# esp_coaster.net
KiCad netlist of a schematic drawn in EAGLE
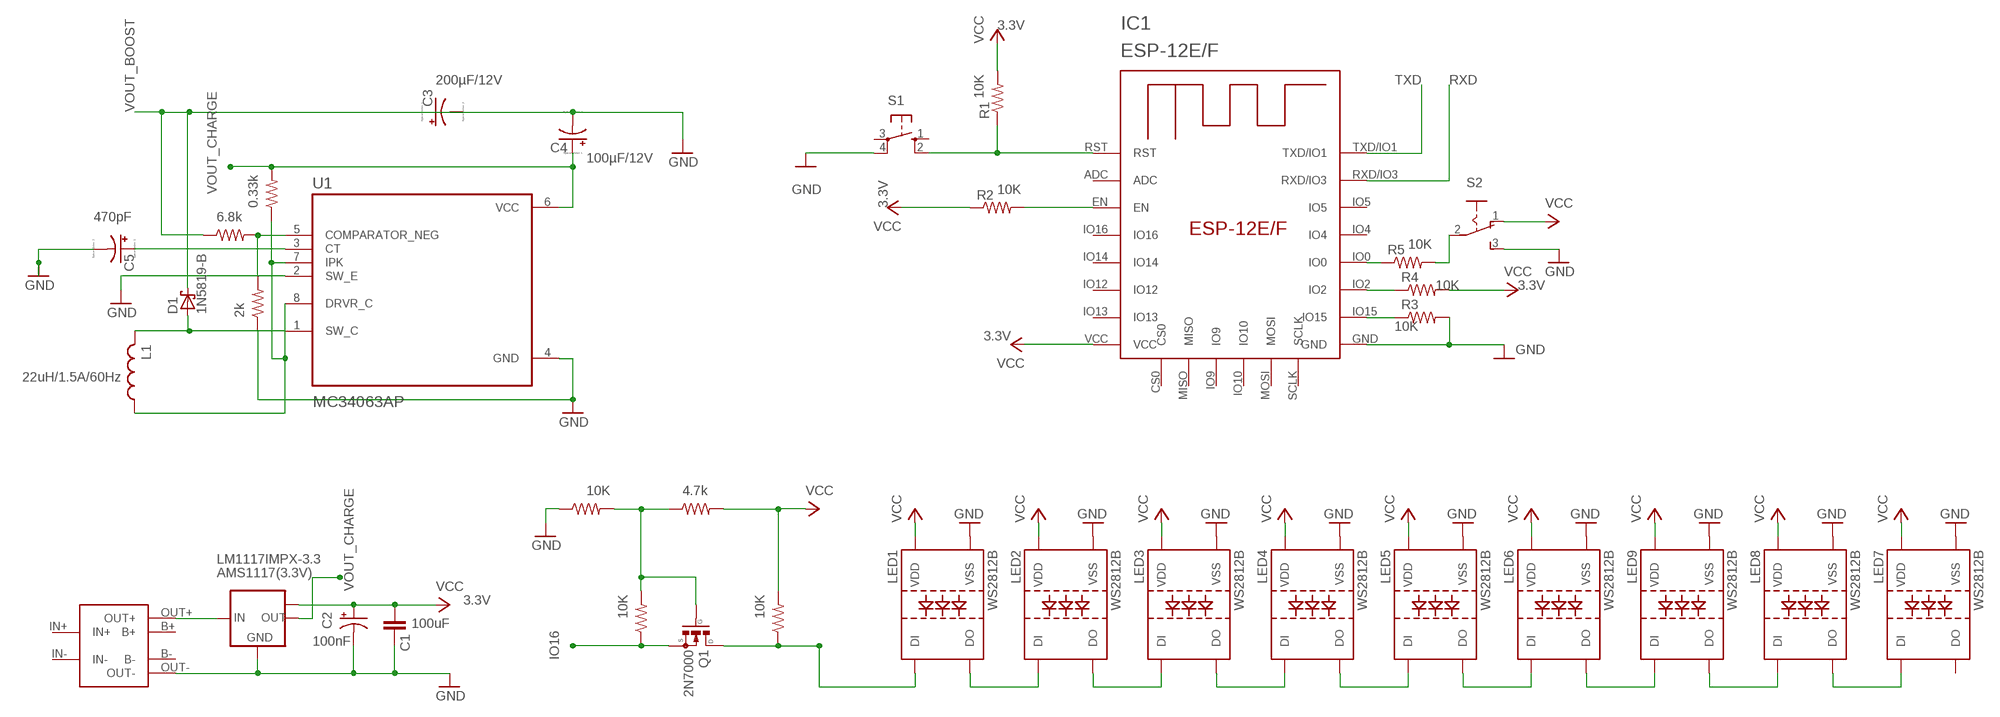
[diagram p0: schematic, sheet 1]

(export (version "E")
  (design (tool "Eeschema 10.0.6"))
  (components
    (comp (ref "AMS1117(3.3V)")
      (value "LM1117IMPX-3.3")
      (footprint "eagle-import:SOT223")
      (libsource (lib "eagle-import") (part "LM1117IMPX-3.3"))
    )
    (comp (ref "C1")
      (value "C-EUC1808")
      (footprint "eagle-import:C1808")
      (fields (field (name "POPULARITY") "0") (field (name "POPULARITY_1") "100uF"))
      (libsource (lib "eagle-import") (part "C-EUC1808"))
    )
    (comp (ref "C2")
      (value "CPOL-US139CLL-2R")
      (footprint "eagle-import:139CLL-2R")
      (fields (field (name "POPULARITY") "0") (field (name "POPULARITY_1") "100nF"))
      (libsource (lib "eagle-import") (part "CPOL-US139CLL-2R"))
    )
    (comp (ref "C3")
      (value "CPOL-US085CS-1AR")
      (footprint "eagle-import:085CS_1AR")
      (fields (field (name "C1") "200µF/12V"))
      (libsource (lib "eagle-import") (part "resistor_348_CPOL-US085CS-1AR"))
    )
    (comp (ref "C4")
      (value "CPOL-US085CS-1AR")
      (footprint "eagle-import:085CS_1AR")
      (fields (field (name "C2") "100µF/12V"))
      (libsource (lib "eagle-import") (part "resistor_348_CPOL-US085CS-1AR"))
    )
    (comp (ref "C5")
      (value "CPOL-US085CS-1AR")
      (footprint "eagle-import:085CS_1AR")
      (fields (field (name "CAPACITOR") "470pF"))
      (libsource (lib "eagle-import") (part "resistor_348_CPOL-US085CS-1AR"))
    )
    (comp (ref "D1")
      (value "1N5819-B")
      (footprint "eagle-import:DO41-7.6")
      (libsource (lib "eagle-import") (part "1N5819-B"))
    )
    (comp (ref "IC1")
      (value "ESP-12E/F")
      (footprint "eagle-import:ESP-12E")
      (libsource (lib "eagle-import") (part "ESP-12E/F"))
    )
    (comp (ref "L1")
      (value "L-US0204/5")
      (footprint "eagle-import:0204_5")
      (fields (field (name "INDUCTOR") "22uH/1.5A/60Hz"))
      (libsource (lib "eagle-import") (part "L-US0204/5"))
    )
    (comp (ref "LED1")
      (value "WS2812B")
      (footprint "eagle-import:WS2812B")
      (libsource (lib "eagle-import") (part "WS2812B"))
    )
    (comp (ref "LED2")
      (value "WS2812B")
      (footprint "eagle-import:WS2812B")
      (libsource (lib "eagle-import") (part "WS2812B"))
    )
    (comp (ref "LED3")
      (value "WS2812B")
      (footprint "eagle-import:WS2812B")
      (libsource (lib "eagle-import") (part "WS2812B"))
    )
    (comp (ref "LED4")
      (value "WS2812B")
      (footprint "eagle-import:WS2812B")
      (libsource (lib "eagle-import") (part "WS2812B"))
    )
    (comp (ref "LED5")
      (value "WS2812B")
      (footprint "eagle-import:WS2812B")
      (libsource (lib "eagle-import") (part "WS2812B"))
    )
    (comp (ref "LED6")
      (value "WS2812B")
      (footprint "eagle-import:WS2812B")
      (libsource (lib "eagle-import") (part "WS2812B"))
    )
    (comp (ref "LED7")
      (value "WS2812B")
      (footprint "eagle-import:WS2812B")
      (libsource (lib "eagle-import") (part "WS2812B"))
    )
    (comp (ref "LED8")
      (value "WS2812B")
      (footprint "eagle-import:WS2812B")
      (libsource (lib "eagle-import") (part "WS2812B"))
    )
    (comp (ref "LED9")
      (value "WS2812B")
      (footprint "eagle-import:WS2812B")
      (libsource (lib "eagle-import") (part "WS2812B"))
    )
    (comp (ref "Q1")
      (value "2N7000")
      (footprint "eagle-import:TO92")
      (fields (field (name "MF") "STMicroelectronics"))
      (libsource (lib "eagle-import") (part "2N7000"))
    )
    (comp (ref "R1")
      (value "R-US_M2309")
      (footprint "eagle-import:M2309")
      (fields (field (name "POPULARITY") "0") (field (name "POPULARITY_1") "10K"))
      (libsource (lib "eagle-import") (part "R-US_M2309"))
    )
    (comp (ref "R2")
      (value "R-US_M2309")
      (footprint "eagle-import:M2309")
      (fields (field (name "POPULARITY") "0") (field (name "POPULARITY_1") "10K"))
      (libsource (lib "eagle-import") (part "R-US_M2309"))
    )
    (comp (ref "R3")
      (value "R-US_M2309")
      (footprint "eagle-import:M2309")
      (fields (field (name "POPULARITY") "0") (field (name "POPULARITY_1") "10K"))
      (libsource (lib "eagle-import") (part "R-US_M2309"))
    )
    (comp (ref "R4")
      (value "R-US_M2309")
      (footprint "eagle-import:M2309")
      (fields (field (name "POPULARITY") "0") (field (name "POPULARITY_1") "10K"))
      (libsource (lib "eagle-import") (part "R-US_M2309"))
    )
    (comp (ref "R5")
      (value "R-US_M2309")
      (footprint "eagle-import:M2309")
      (fields (field (name "POPULARITY") "0") (field (name "POPULARITY_1") "10K"))
      (libsource (lib "eagle-import") (part "R-US_M2309"))
    )
    (comp (ref "R6")
      (value "R-US_M2309")
      (footprint "eagle-import:M2309")
      (fields (field (name "POPULARITY") "0") (field (name "POPULARITY_1") "6.8k"))
      (libsource (lib "eagle-import") (part "R-US_M2309"))
    )
    (comp (ref "R7")
      (value "R-US_M2309")
      (footprint "eagle-import:M2309")
      (fields (field (name "POPULARITY") "0") (field (name "POPULARITY_1") "2k"))
      (libsource (lib "eagle-import") (part "R-US_M2309"))
    )
    (comp (ref "R8")
      (value "R-US_M2309")
      (footprint "eagle-import:M2309")
      (fields (field (name "POPULARITY") "0") (field (name "POPULARITY_1") "0.33k"))
      (libsource (lib "eagle-import") (part "R-US_M2309"))
    )
    (comp (ref "R9")
      (value "R-US_M2309")
      (footprint "eagle-import:M2309")
      (fields (field (name "POPULARITY") "0") (field (name "POPULARITY_1") "10K"))
      (libsource (lib "eagle-import") (part "R-US_M2309"))
    )
    (comp (ref "R10")
      (value "R-US_M2309")
      (footprint "eagle-import:M2309")
      (fields (field (name "POPULARITY") "0") (field (name "POPULARITY_1") "4.7k"))
      (libsource (lib "eagle-import") (part "R-US_M2309"))
    )
    (comp (ref "R11")
      (value "R-US_M2309")
      (footprint "eagle-import:M2309")
      (fields (field (name "POPULARITY") "0") (field (name "POPULARITY_1") "10K"))
      (libsource (lib "eagle-import") (part "R-US_M2309"))
    )
    (comp (ref "R12")
      (value "R-US_M2309")
      (footprint "eagle-import:M2309")
      (fields (field (name "POPULARITY") "0") (field (name "POPULARITY_1") "10K"))
      (libsource (lib "eagle-import") (part "R-US_M2309"))
    )
    (comp (ref "S1")
      (value "10-XX")
      (footprint "eagle-import:B3F-10XX")
      (fields (field (name "MPN") "B3F-1000"))
      (libsource (lib "eagle-import") (part "10-XX"))
    )
    (comp (ref "S2")
      (value "255SB")
      (footprint "eagle-import:255SB")
      (libsource (lib "eagle-import") (part "255SB"))
    )
    (comp (ref "U$1")
      (value "TP4056")
      (footprint "eagle-import:TP4056")
      (libsource (lib "eagle-import") (part "TP4056"))
    )
    (comp (ref "U1")
      (value "MC34063AP")
      (footprint "eagle-import:DIP794W45P254L959H508Q8")
      (fields (field (name "MF") "Texas Instruments"))
      (libsource (lib "eagle-import") (part "MC34063AP"))
    )
  )
  (nets
    (net (code "1") (name "/IO16") (class "Default")
      (node (ref "Q1") (pin "1") (pinfunction "S_1") (pintype "passive"))
      (node (ref "R12") (pin "1") (pinfunction "1_1") (pintype "passive"))
    )
    (net (code "2") (name "/RXD") (class "Default")
      (node (ref "IC1") (pin "RXD/IO3") (pinfunction "RXD/IO3_RXD/IO3") (pintype "bidirectional"))
    )
    (net (code "3") (name "/TXD") (class "Default")
      (node (ref "IC1") (pin "TXD/IO1") (pinfunction "TXD/IO1_TXD/IO1") (pintype "bidirectional"))
    )
    (net (code "4") (name "/VOUT_BOOST") (class "Default")
      (node (ref "C3") (pin "-") (pinfunction "-_-") (pintype "passive"))
      (node (ref "D1") (pin "C") (pinfunction "C_C") (pintype "passive"))
      (node (ref "R6") (pin "1") (pinfunction "1_1") (pintype "passive"))
    )
    (net (code "5") (name "/VOUT_CHARGE") (class "Default")
      (node (ref "AMS1117(3.3V)") (pin "2") (pinfunction "OUT_2") (pintype "passive"))
      (node (ref "C4") (pin "+") (pinfunction "+_+") (pintype "passive"))
      (node (ref "R8") (pin "2") (pinfunction "2_2") (pintype "passive"))
      (node (ref "U1") (pin "6") (pinfunction "VCC_6") (pintype "power_in"))
    )
    (net (code "6") (name "GND") (class "Default")
      (node (ref "AMS1117(3.3V)") (pin "1") (pinfunction "GND_1") (pintype "input"))
      (node (ref "C1") (pin "1") (pinfunction "1_1") (pintype "passive"))
      (node (ref "C2") (pin "-") (pinfunction "-_-") (pintype "passive"))
      (node (ref "C3") (pin "+") (pinfunction "+_+") (pintype "passive"))
      (node (ref "C4") (pin "-") (pinfunction "-_-") (pintype "passive"))
      (node (ref "C5") (pin "-") (pinfunction "-_-") (pintype "passive"))
      (node (ref "IC1") (pin "GND") (pinfunction "GND_GND") (pintype "power_in"))
      (node (ref "LED1") (pin "3") (pinfunction "VSS_3") (pintype "bidirectional"))
      (node (ref "LED2") (pin "3") (pinfunction "VSS_3") (pintype "bidirectional"))
      (node (ref "LED3") (pin "3") (pinfunction "VSS_3") (pintype "bidirectional"))
      (node (ref "LED4") (pin "3") (pinfunction "VSS_3") (pintype "bidirectional"))
      (node (ref "LED5") (pin "3") (pinfunction "VSS_3") (pintype "bidirectional"))
      (node (ref "LED6") (pin "3") (pinfunction "VSS_3") (pintype "bidirectional"))
      (node (ref "LED7") (pin "3") (pinfunction "VSS_3") (pintype "bidirectional"))
      (node (ref "LED8") (pin "3") (pinfunction "VSS_3") (pintype "bidirectional"))
      (node (ref "LED9") (pin "3") (pinfunction "VSS_3") (pintype "bidirectional"))
      (node (ref "R11") (pin "1") (pinfunction "1_1") (pintype "passive"))
      (node (ref "R3") (pin "2") (pinfunction "2_2") (pintype "passive"))
      (node (ref "R7") (pin "1") (pinfunction "1_1") (pintype "passive"))
      (node (ref "S1") (pin "4") (pinfunction "P1_4") (pintype "passive"))
      (node (ref "S2") (pin "3") (pinfunction "S_3") (pintype "passive"))
      (node (ref "U$1") (pin "OUT-") (pinfunction "OUT-_OUT-") (pintype "bidirectional"))
      (node (ref "U1") (pin "2") (pinfunction "SW_E_2") (pintype "input"))
      (node (ref "U1") (pin "4") (pinfunction "GND_4") (pintype "power_in"))
    )
    (net (code "7") (name "Net-(AMS1117(3.3V)-IN)") (class "Default")
      (node (ref "AMS1117(3.3V)") (pin "3") (pinfunction "IN_3") (pintype "input"))
      (node (ref "U$1") (pin "OUT+") (pinfunction "OUT+_OUT+") (pintype "bidirectional"))
    )
    (net (code "8") (name "Net-(IC1-PadEN)") (class "Default")
      (node (ref "IC1") (pin "EN") (pinfunction "EN_EN") (pintype "bidirectional"))
      (node (ref "R2") (pin "2") (pinfunction "2_2") (pintype "passive"))
    )
    (net (code "9") (name "Net-(IC1-PadIO0)") (class "Default")
      (node (ref "IC1") (pin "IO0") (pinfunction "IO0_IO0") (pintype "bidirectional"))
      (node (ref "R5") (pin "1") (pinfunction "1_1") (pintype "passive"))
    )
    (net (code "10") (name "Net-(IC1-PadIO2)") (class "Default")
      (node (ref "IC1") (pin "IO2") (pinfunction "IO2_IO2") (pintype "bidirectional"))
      (node (ref "R4") (pin "1") (pinfunction "1_1") (pintype "passive"))
    )
    (net (code "11") (name "Net-(IC1-PadIO15)") (class "Default")
      (node (ref "IC1") (pin "IO15") (pinfunction "IO15_IO15") (pintype "bidirectional"))
      (node (ref "R3") (pin "1") (pinfunction "1_1") (pintype "passive"))
    )
    (net (code "12") (name "Net-(LED1-DI)") (class "Default")
      (node (ref "LED1") (pin "4") (pinfunction "DI_4") (pintype "bidirectional"))
      (node (ref "Q1") (pin "3") (pinfunction "D_3") (pintype "passive"))
      (node (ref "R9") (pin "1") (pinfunction "1_1") (pintype "passive"))
    )
    (net (code "13") (name "Net-(LED1-DO)") (class "Default")
      (node (ref "LED1") (pin "2") (pinfunction "DO_2") (pintype "bidirectional"))
      (node (ref "LED2") (pin "4") (pinfunction "DI_4") (pintype "bidirectional"))
    )
    (net (code "14") (name "Net-(LED2-DO)") (class "Default")
      (node (ref "LED2") (pin "2") (pinfunction "DO_2") (pintype "bidirectional"))
      (node (ref "LED3") (pin "4") (pinfunction "DI_4") (pintype "bidirectional"))
    )
    (net (code "15") (name "Net-(LED3-DO)") (class "Default")
      (node (ref "LED3") (pin "2") (pinfunction "DO_2") (pintype "bidirectional"))
      (node (ref "LED4") (pin "4") (pinfunction "DI_4") (pintype "bidirectional"))
    )
    (net (code "16") (name "Net-(LED4-DO)") (class "Default")
      (node (ref "LED4") (pin "2") (pinfunction "DO_2") (pintype "bidirectional"))
      (node (ref "LED5") (pin "4") (pinfunction "DI_4") (pintype "bidirectional"))
    )
    (net (code "17") (name "Net-(LED5-DO)") (class "Default")
      (node (ref "LED5") (pin "2") (pinfunction "DO_2") (pintype "bidirectional"))
      (node (ref "LED6") (pin "4") (pinfunction "DI_4") (pintype "bidirectional"))
    )
    (net (code "18") (name "Net-(LED6-DO)") (class "Default")
      (node (ref "LED6") (pin "2") (pinfunction "DO_2") (pintype "bidirectional"))
      (node (ref "LED9") (pin "4") (pinfunction "DI_4") (pintype "bidirectional"))
    )
    (net (code "19") (name "Net-(LED7-DI)") (class "Default")
      (node (ref "LED7") (pin "4") (pinfunction "DI_4") (pintype "bidirectional"))
      (node (ref "LED8") (pin "2") (pinfunction "DO_2") (pintype "bidirectional"))
    )
    (net (code "20") (name "Net-(LED8-DI)") (class "Default")
      (node (ref "LED8") (pin "4") (pinfunction "DI_4") (pintype "bidirectional"))
      (node (ref "LED9") (pin "2") (pinfunction "DO_2") (pintype "bidirectional"))
    )
    (net (code "21") (name "Net-(Q1-G)") (class "Default")
      (node (ref "Q1") (pin "2") (pinfunction "G_2") (pintype "passive"))
      (node (ref "R10") (pin "1") (pinfunction "1_1") (pintype "passive"))
      (node (ref "R11") (pin "2") (pinfunction "2_2") (pintype "passive"))
      (node (ref "R12") (pin "2") (pinfunction "2_2") (pintype "passive"))
    )
    (net (code "22") (name "Net-(S1-S1)") (class "Default")
      (node (ref "IC1") (pin "RST") (pinfunction "RST_RST") (pintype "input"))
      (node (ref "R1") (pin "1") (pinfunction "1_1") (pintype "passive"))
      (node (ref "S1") (pin "2") (pinfunction "S1_2") (pintype "passive"))
    )
    (net (code "23") (name "Net-(S2-P)") (class "Default")
      (node (ref "R5") (pin "2") (pinfunction "2_2") (pintype "passive"))
      (node (ref "S2") (pin "2") (pinfunction "P_2") (pintype "passive"))
    )
    (net (code "24") (name "Net-(U1-COMPARATOR_NEG)") (class "Default")
      (node (ref "R6") (pin "2") (pinfunction "2_2") (pintype "passive"))
      (node (ref "R7") (pin "2") (pinfunction "2_2") (pintype "passive"))
      (node (ref "U1") (pin "5") (pinfunction "COMPARATOR_NEG_5") (pintype "input"))
    )
    (net (code "25") (name "Net-(U1-CT)") (class "Default")
      (node (ref "C5") (pin "+") (pinfunction "+_+") (pintype "passive"))
      (node (ref "U1") (pin "3") (pinfunction "CT_3") (pintype "input"))
    )
    (net (code "26") (name "Net-(U1-DRVR_C)") (class "Default")
      (node (ref "L1") (pin "1") (pinfunction "1_1") (pintype "passive"))
      (node (ref "R8") (pin "1") (pinfunction "1_1") (pintype "passive"))
      (node (ref "U1") (pin "7") (pinfunction "IPK_7") (pintype "input"))
      (node (ref "U1") (pin "8") (pinfunction "DRVR_C_8") (pintype "bidirectional"))
    )
    (net (code "27") (name "Net-(U1-SW_C)") (class "Default")
      (node (ref "D1") (pin "A") (pinfunction "A_A") (pintype "passive"))
      (node (ref "L1") (pin "2") (pinfunction "2_2") (pintype "passive"))
      (node (ref "U1") (pin "1") (pinfunction "SW_C_1") (pintype "bidirectional"))
    )
    (net (code "28") (name "VCC") (class "Default")
      (node (ref "AMS1117(3.3V)") (pin "TAB") (pinfunction "OUT1_TAB") (pintype "passive"))
      (node (ref "C1") (pin "2") (pinfunction "2_2") (pintype "passive"))
      (node (ref "C2") (pin "+") (pinfunction "+_+") (pintype "passive"))
      (node (ref "IC1") (pin "VCC") (pinfunction "VCC_VCC") (pintype "power_in"))
      (node (ref "LED1") (pin "1") (pinfunction "VDD_1") (pintype "bidirectional"))
      (node (ref "LED2") (pin "1") (pinfunction "VDD_1") (pintype "bidirectional"))
      (node (ref "LED3") (pin "1") (pinfunction "VDD_1") (pintype "bidirectional"))
      (node (ref "LED4") (pin "1") (pinfunction "VDD_1") (pintype "bidirectional"))
      (node (ref "LED5") (pin "1") (pinfunction "VDD_1") (pintype "bidirectional"))
      (node (ref "LED6") (pin "1") (pinfunction "VDD_1") (pintype "bidirectional"))
      (node (ref "LED7") (pin "1") (pinfunction "VDD_1") (pintype "bidirectional"))
      (node (ref "LED8") (pin "1") (pinfunction "VDD_1") (pintype "bidirectional"))
      (node (ref "LED9") (pin "1") (pinfunction "VDD_1") (pintype "bidirectional"))
      (node (ref "R1") (pin "2") (pinfunction "2_2") (pintype "passive"))
      (node (ref "R10") (pin "2") (pinfunction "2_2") (pintype "passive"))
      (node (ref "R2") (pin "1") (pinfunction "1_1") (pintype "passive"))
      (node (ref "R4") (pin "2") (pinfunction "2_2") (pintype "passive"))
      (node (ref "R9") (pin "2") (pinfunction "2_2") (pintype "passive"))
      (node (ref "S2") (pin "1") (pinfunction "O_1") (pintype "passive"))
    )
    (net (code "29") (name "unconnected-(IC1-PadADC)") (class "Default")
      (node (ref "IC1") (pin "ADC") (pinfunction "ADC_ADC") (pintype "bidirectional"))
    )
    (net (code "30") (name "unconnected-(IC1-PadCS0)") (class "Default")
      (node (ref "IC1") (pin "CS0") (pinfunction "CS0_CS0") (pintype "bidirectional"))
    )
    (net (code "31") (name "unconnected-(IC1-PadIO4)") (class "Default")
      (node (ref "IC1") (pin "IO4") (pinfunction "IO4_IO4") (pintype "bidirectional"))
    )
    (net (code "32") (name "unconnected-(IC1-PadIO5)") (class "Default")
      (node (ref "IC1") (pin "IO5") (pinfunction "IO5_IO5") (pintype "bidirectional"))
    )
    (net (code "33") (name "unconnected-(IC1-PadIO9)") (class "Default")
      (node (ref "IC1") (pin "IO9") (pinfunction "IO9_IO9") (pintype "bidirectional"))
    )
    (net (code "34") (name "unconnected-(IC1-PadIO10)") (class "Default")
      (node (ref "IC1") (pin "IO10") (pinfunction "IO10_IO10") (pintype "bidirectional"))
    )
    (net (code "35") (name "unconnected-(IC1-PadIO12)") (class "Default")
      (node (ref "IC1") (pin "IO12") (pinfunction "IO12_IO12") (pintype "bidirectional"))
    )
    (net (code "36") (name "unconnected-(IC1-PadIO13)") (class "Default")
      (node (ref "IC1") (pin "IO13") (pinfunction "IO13_IO13") (pintype "bidirectional"))
    )
    (net (code "37") (name "unconnected-(IC1-PadIO14)") (class "Default")
      (node (ref "IC1") (pin "IO14") (pinfunction "IO14_IO14") (pintype "bidirectional"))
    )
    (net (code "38") (name "unconnected-(IC1-PadIO16)") (class "Default")
      (node (ref "IC1") (pin "IO16") (pinfunction "IO16_IO16") (pintype "bidirectional"))
    )
    (net (code "39") (name "unconnected-(IC1-PadMISO)") (class "Default")
      (node (ref "IC1") (pin "MISO") (pinfunction "MISO_MISO") (pintype "bidirectional"))
    )
    (net (code "40") (name "unconnected-(IC1-PadMOSI)") (class "Default")
      (node (ref "IC1") (pin "MOSI") (pinfunction "MOSI_MOSI") (pintype "bidirectional"))
    )
    (net (code "41") (name "unconnected-(IC1-PadSCLK)") (class "Default")
      (node (ref "IC1") (pin "SCLK") (pinfunction "SCLK_SCLK") (pintype "bidirectional"))
    )
    (net (code "42") (name "unconnected-(LED7-DO-Pad2)") (class "Default")
      (node (ref "LED7") (pin "2") (pinfunction "DO_2") (pintype "bidirectional"))
    )
    (net (code "43") (name "unconnected-(S1-P-Pad3)") (class "Default")
      (node (ref "S1") (pin "3") (pinfunction "P_3") (pintype "passive"))
    )
    (net (code "44") (name "unconnected-(S1-S-Pad1)") (class "Default")
      (node (ref "S1") (pin "1") (pinfunction "S_1") (pintype "passive"))
    )
    (net (code "45") (name "unconnected-(U$1-PadB+)") (class "Default")
      (node (ref "U$1") (pin "B+") (pinfunction "B+_B+") (pintype "bidirectional"))
    )
    (net (code "46") (name "unconnected-(U$1-PadB-)") (class "Default")
      (node (ref "U$1") (pin "B-") (pinfunction "B-_B-") (pintype "bidirectional"))
    )
    (net (code "47") (name "unconnected-(U$1-PadIN+)") (class "Default")
      (node (ref "U$1") (pin "IN+") (pinfunction "IN+_IN+") (pintype "bidirectional"))
    )
    (net (code "48") (name "unconnected-(U$1-PadIN-)") (class "Default")
      (node (ref "U$1") (pin "IN-") (pinfunction "IN-_IN-") (pintype "bidirectional"))
    )
  )
)
